# as5311-module.net
KiCad netlist of a schematic drawn in Altium Designer
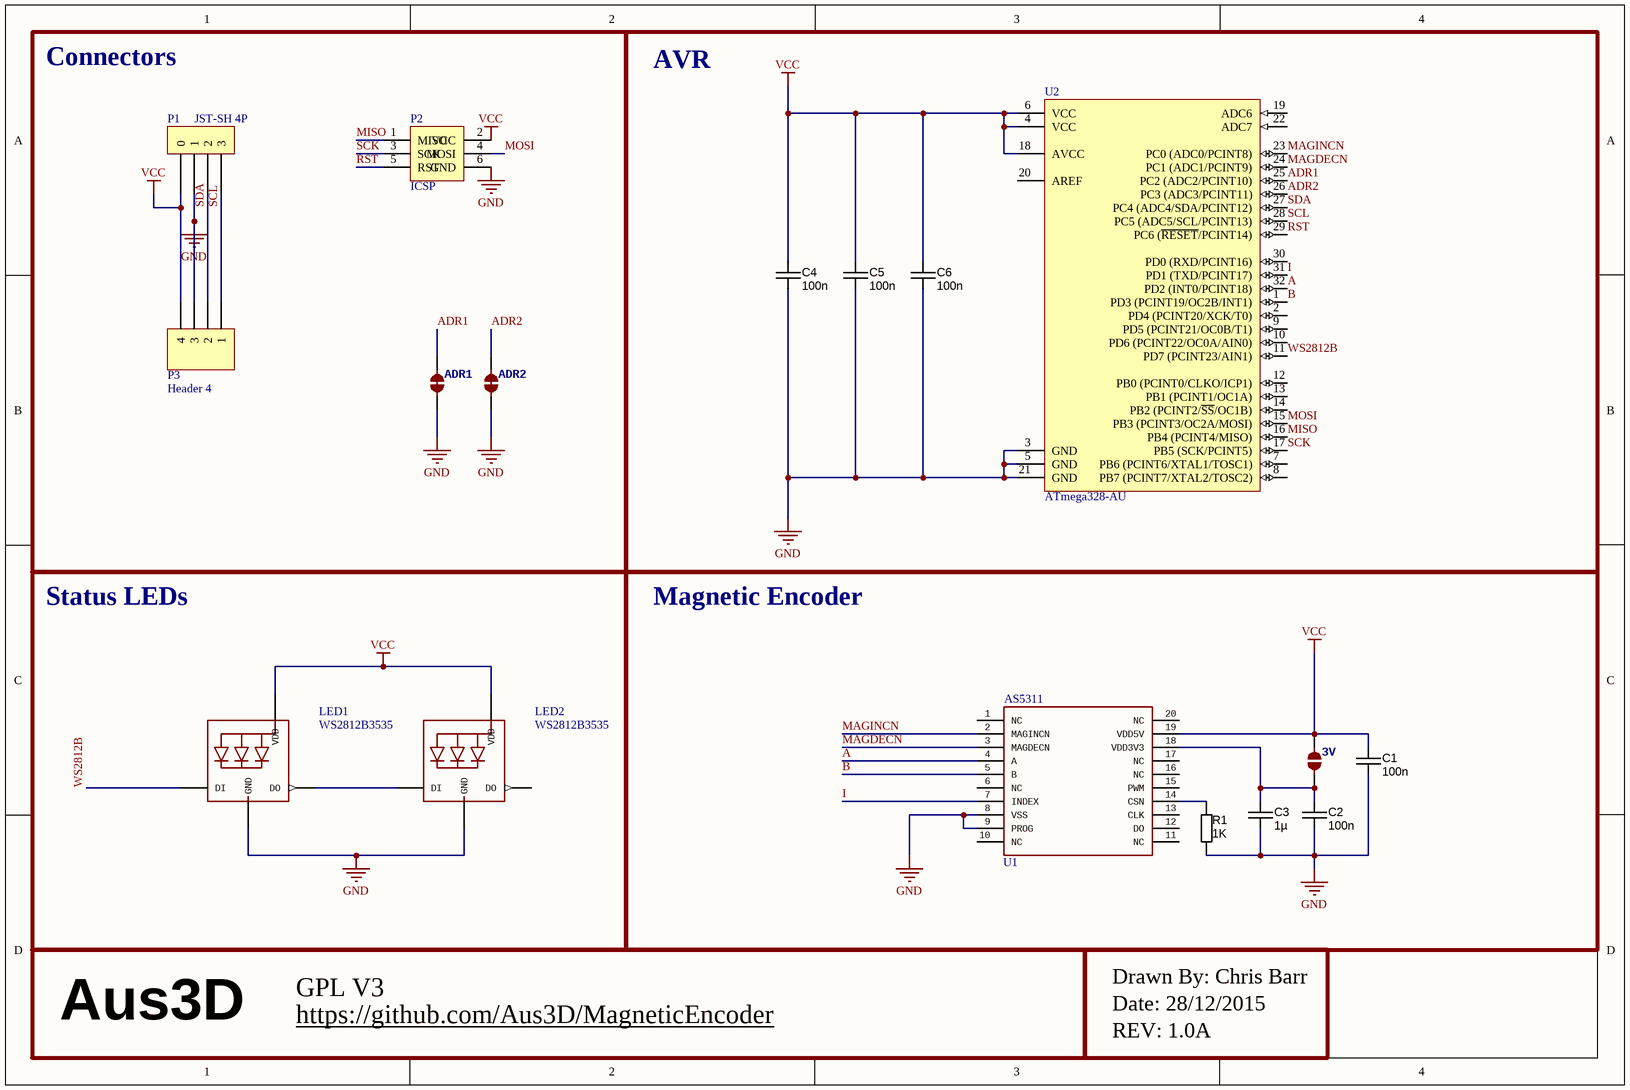
[diagram p0: as5311-module.SchDoc]

(export (version "E")
  (design (tool "Eeschema 10.0.6"))
  (components
    (comp (ref "3V")
      (value "JUMPER-PAD-2-NO")
      (footprint "PAD-JUMPER-2-NO_NO_SILK")
      (libsource (lib "SparkFun-Passives") (part "JUMPER-PAD-2-NO"))
    )
    (comp (ref "ADR1")
      (value "JUMPER-PAD-2-NC_BY_TRACE")
      (footprint "PAD-JUMPER-2-NC_BY_TRACE_YES_SILK")
      (libsource (lib "SparkFun-Passives") (part "JUMPER-PAD-2-NC_BY_TRACE"))
    )
    (comp (ref "ADR2")
      (value "JUMPER-PAD-2-NC_BY_TRACE")
      (footprint "PAD-JUMPER-2-NC_BY_TRACE_YES_SILK")
      (libsource (lib "SparkFun-Passives") (part "JUMPER-PAD-2-NC_BY_TRACE"))
    )
    (comp (ref "C1")
      (value "100n")
      (footprint "CAPC1608X90N")
      (description "Capacitor SMD Cer 100nF 10% 50V X7R 0603")
      (fields (field (name "TOLERANCE") "±10%") (field (name "Comment") "approved sub OK"))
      (libsource (lib "PBL - Capacitors") (part "CAPC_100n_0603_X7R_50V_10%"))
    )
    (comp (ref "C2")
      (value "100n")
      (footprint "CAPC1608X90N")
      (description "Capacitor SMD Cer 100nF 10% 50V X7R 0603")
      (fields (field (name "TOLERANCE") "±10%") (field (name "Comment") "approved sub OK"))
      (libsource (lib "PBL - Capacitors") (part "CAPC_100n_0603_X7R_50V_10%"))
    )
    (comp (ref "C3")
      (value "1µ")
      (footprint "CAPC1608X90N")
      (description "Capacitor SMD Cer 1uF 10% 16V X7R 0603")
      (fields (field (name "TOLERANCE") "±10%") (field (name "Comment") "approved sub OK"))
      (libsource (lib "PBL - Capacitors") (part "CAPC_1u_0603_X7R_16V_10%"))
    )
    (comp (ref "C4")
      (value "100n")
      (footprint "CAPC1608X90N")
      (description "Capacitor SMD Cer 100nF 10% 50V X7R 0603")
      (fields (field (name "TOLERANCE") "±10%") (field (name "Comment") "approved sub OK"))
      (libsource (lib "PBL - Capacitors") (part "CAPC_100n_0603_X7R_50V_10%"))
    )
    (comp (ref "C5")
      (value "100n")
      (footprint "CAPC1608X90N")
      (description "Capacitor SMD Cer 100nF 10% 50V X7R 0603")
      (fields (field (name "TOLERANCE") "±10%") (field (name "Comment") "approved sub OK"))
      (libsource (lib "PBL - Capacitors") (part "CAPC_100n_0603_X7R_50V_10%"))
    )
    (comp (ref "C6")
      (value "100n")
      (footprint "CAPC1608X90N")
      (description "Capacitor SMD Cer 100nF 10% 50V X7R 0603")
      (fields (field (name "TOLERANCE") "±10%") (field (name "Comment") "approved sub OK"))
      (libsource (lib "PBL - Capacitors") (part "CAPC_100n_0603_X7R_50V_10%"))
    )
    (comp (ref "LED1")
      (value "WS2812B3535")
      (footprint "LED3535")
      (libsource (lib "adafruit") (part "WS2812B3535"))
    )
    (comp (ref "LED2")
      (value "WS2812B3535")
      (footprint "LED3535")
      (libsource (lib "adafruit") (part "WS2812B3535"))
    )
    (comp (ref "P1")
      (value "JST-SH 4P")
      (footprint "SM04B-SRSS-TB")
      (libsource (lib "Schlib1") (part "SM04B-SRSS-TB"))
    )
    (comp (ref "P2")
      (value "ICSP")
      (footprint "ICSP Pads - SMD")
      (description "Header, 3-Pin, Dual row")
      (fields (field (name "PUBLISHER") "Altium Limited"))
      (libsource (lib "Miscellaneous Connectors") (part "Header 3X2"))
    )
    (comp (ref "P3")
      (value "Header 4")
      (footprint "HDR1X4")
      (description "Header, 4-Pin")
      (fields (field (name "PUBLISHER") "Altium Limited"))
      (libsource (lib "Miscellaneous Connectors") (part "Header 4"))
    )
    (comp (ref "R1")
      (value "1K")
      (footprint "RESC1608X55N")
      (description "Resistor SMD chip 1k Ohm 0.1W 5% 0603")
      (fields (field (name "TOLERANCE") "±5%") (field (name "Comment") "Thick Film"))
      (libsource (lib "PBL - Resistors") (part "RES_1K_0603_5%"))
    )
    (comp (ref "U1")
      (value "AS5311")
      (footprint "TSSOP-20")
      (description "AMS's AS5311 linear hall-effect encoder.")
      (libsource (lib "ams") (part "AS5311"))
    )
    (comp (ref "U2")
      (value "ATmega328-AU")
      (footprint "32A_N")
      (libsource (lib "Atmel Microcontroller megaAVR") (part "ATmega328-AU"))
    )
  )
  (nets
    (net (code "1") (name "/A") (class "Default")
      (node (ref "U1") (pin "4") (pinfunction "A_4") (pintype "passive"))
      (node (ref "U2") (pin "32") (pinfunction "PD2_(INT0/PCINT18)_32") (pintype "bidirectional"))
    )
    (net (code "2") (name "/ADR1") (class "Default")
      (node (ref "ADR1") (pin "2") (pinfunction "2_2") (pintype "passive"))
      (node (ref "U2") (pin "25") (pinfunction "PC2_(ADC2/PCINT10)_25") (pintype "bidirectional"))
    )
    (net (code "3") (name "/ADR2") (class "Default")
      (node (ref "ADR2") (pin "2") (pinfunction "2_2") (pintype "passive"))
      (node (ref "U2") (pin "26") (pinfunction "PC3_(ADC3/PCINT11)_26") (pintype "bidirectional"))
    )
    (net (code "4") (name "/B") (class "Default")
      (node (ref "U1") (pin "5") (pinfunction "B_5") (pintype "passive"))
      (node (ref "U2") (pin "1") (pinfunction "PD3_(PCINT19/OC2B/INT1)_1") (pintype "bidirectional"))
    )
    (net (code "5") (name "/I") (class "Default")
      (node (ref "U1") (pin "7") (pinfunction "INDEX_7") (pintype "passive"))
      (node (ref "U2") (pin "31") (pinfunction "PD1_(TXD/PCINT17)_31") (pintype "bidirectional"))
    )
    (net (code "6") (name "/MAGDECN") (class "Default")
      (node (ref "U1") (pin "3") (pinfunction "MAGDECN_3") (pintype "passive"))
      (node (ref "U2") (pin "24") (pinfunction "PC1_(ADC1/PCINT9)_24") (pintype "bidirectional"))
    )
    (net (code "7") (name "/MAGINCN") (class "Default")
      (node (ref "U1") (pin "2") (pinfunction "MAGINCN_2") (pintype "passive"))
      (node (ref "U2") (pin "23") (pinfunction "PC0_(ADC0/PCINT8)_23") (pintype "bidirectional"))
    )
    (net (code "8") (name "/MISO") (class "Default")
      (node (ref "P2") (pin "1") (pinfunction "MISO_1") (pintype "passive"))
      (node (ref "U2") (pin "16") (pinfunction "PB4_(PCINT4/MISO)_16") (pintype "bidirectional"))
    )
    (net (code "9") (name "/MOSI") (class "Default")
      (node (ref "P2") (pin "4") (pinfunction "MOSI_4") (pintype "passive"))
      (node (ref "U2") (pin "15") (pinfunction "PB3_(PCINT3/OC2A/MOSI)_15") (pintype "bidirectional"))
    )
    (net (code "10") (name "/RST") (class "Default")
      (node (ref "P2") (pin "5") (pinfunction "RST_5") (pintype "passive"))
      (node (ref "U2") (pin "29") (pinfunction "PC6_(~{RESET}/PCINT14)_29") (pintype "bidirectional"))
    )
    (net (code "11") (name "/SCK") (class "Default")
      (node (ref "P2") (pin "3") (pinfunction "SCK_3") (pintype "passive"))
      (node (ref "U2") (pin "17") (pinfunction "PB5_(SCK/PCINT5)_17") (pintype "bidirectional"))
    )
    (net (code "12") (name "/SCL") (class "Default")
      (node (ref "P1") (pin "3") (pinfunction "3_3") (pintype "passive"))
      (node (ref "P3") (pin "1") (pinfunction "1_1") (pintype "passive"))
      (node (ref "U2") (pin "28") (pinfunction "PC5_(ADC5/SCL/PCINT13)_28") (pintype "bidirectional"))
    )
    (net (code "13") (name "/SDA") (class "Default")
      (node (ref "P1") (pin "2") (pinfunction "2_2") (pintype "passive"))
      (node (ref "P3") (pin "2") (pinfunction "2_2") (pintype "passive"))
      (node (ref "U2") (pin "27") (pinfunction "PC4_(ADC4/SDA/PCINT12)_27") (pintype "bidirectional"))
    )
    (net (code "14") (name "/WS2812B") (class "Default")
      (node (ref "LED1") (pin "1") (pinfunction "DI_1") (pintype "passive"))
      (node (ref "U2") (pin "11") (pinfunction "PD7_(PCINT23/AIN1)_11") (pintype "bidirectional"))
    )
    (net (code "15") (name "GND") (class "Default")
      (node (ref "ADR1") (pin "1") (pinfunction "1_1") (pintype "passive"))
      (node (ref "ADR2") (pin "1") (pinfunction "1_1") (pintype "passive"))
      (node (ref "C1") (pin "2") (pintype "passive"))
      (node (ref "C2") (pin "2") (pintype "passive"))
      (node (ref "C3") (pin "2") (pintype "passive"))
      (node (ref "C4") (pin "2") (pintype "passive"))
      (node (ref "C5") (pin "2") (pintype "passive"))
      (node (ref "C6") (pin "2") (pintype "passive"))
      (node (ref "LED1") (pin "4") (pinfunction "GND_4") (pintype "power_in"))
      (node (ref "LED2") (pin "4") (pinfunction "GND_4") (pintype "power_in"))
      (node (ref "P1") (pin "1") (pinfunction "1_1") (pintype "passive"))
      (node (ref "P2") (pin "6") (pinfunction "GND_6") (pintype "passive"))
      (node (ref "P3") (pin "3") (pinfunction "3_3") (pintype "passive"))
      (node (ref "R1") (pin "2") (pinfunction "2_2") (pintype "passive"))
      (node (ref "U1") (pin "8") (pinfunction "VSS_8") (pintype "power_in"))
      (node (ref "U1") (pin "9") (pinfunction "PROG_9") (pintype "passive"))
      (node (ref "U2") (pin "21") (pinfunction "GND_21") (pintype "power_in"))
      (node (ref "U2") (pin "3") (pinfunction "GND_3") (pintype "power_in"))
      (node (ref "U2") (pin "5") (pinfunction "GND_5") (pintype "power_in"))
    )
    (net (code "16") (name "Net-(LED1-DO)") (class "Default")
      (node (ref "LED1") (pin "3") (pinfunction "DO_3") (pintype "output"))
      (node (ref "LED2") (pin "1") (pinfunction "DI_1") (pintype "passive"))
    )
    (net (code "17") (name "Net-(U1-CSN)") (class "Default")
      (node (ref "R1") (pin "1") (pinfunction "1_1") (pintype "passive"))
      (node (ref "U1") (pin "14") (pinfunction "CSN_14") (pintype "passive"))
    )
    (net (code "18") (name "Net-(U1-VDD3V3)") (class "Default")
      (node (ref "3V") (pin "1") (pinfunction "1_1") (pintype "passive"))
      (node (ref "C2") (pin "1") (pintype "passive"))
      (node (ref "C3") (pin "1") (pintype "passive"))
      (node (ref "U1") (pin "18") (pinfunction "VDD3V3_18") (pintype "open_emitter"))
    )
    (net (code "19") (name "VCC") (class "Default")
      (node (ref "3V") (pin "2") (pinfunction "2_2") (pintype "passive"))
      (node (ref "C1") (pin "1") (pintype "passive"))
      (node (ref "C4") (pin "1") (pintype "passive"))
      (node (ref "C5") (pin "1") (pintype "passive"))
      (node (ref "C6") (pin "1") (pintype "passive"))
      (node (ref "LED1") (pin "2") (pinfunction "VDD_2") (pintype "power_in"))
      (node (ref "LED2") (pin "2") (pinfunction "VDD_2") (pintype "power_in"))
      (node (ref "P1") (pin "0") (pinfunction "0_0") (pintype "passive"))
      (node (ref "P2") (pin "2") (pinfunction "VCC_2") (pintype "passive"))
      (node (ref "P3") (pin "4") (pinfunction "4_4") (pintype "passive"))
      (node (ref "U1") (pin "19") (pinfunction "VDD5V_19") (pintype "open_emitter"))
      (node (ref "U2") (pin "18") (pinfunction "AVCC_18") (pintype "power_in"))
      (node (ref "U2") (pin "4") (pinfunction "VCC_4") (pintype "power_in"))
      (node (ref "U2") (pin "6") (pinfunction "VCC_6") (pintype "power_in"))
    )
    (net (code "20") (name "unconnected-(LED2-DO-Pad3)") (class "Default")
      (node (ref "LED2") (pin "3") (pinfunction "DO_3") (pintype "output"))
    )
    (net (code "21") (name "unconnected-(U1-CLK-Pad13)") (class "Default")
      (node (ref "U1") (pin "13") (pinfunction "CLK_13") (pintype "passive"))
    )
    (net (code "22") (name "unconnected-(U1-DO-Pad12)") (class "Default")
      (node (ref "U1") (pin "12") (pinfunction "DO_12") (pintype "passive"))
    )
    (net (code "23") (name "unconnected-(U1-NC-Pad1)") (class "Default")
      (node (ref "U1") (pin "1") (pinfunction "NC_1") (pintype "passive"))
    )
    (net (code "24") (name "unconnected-(U1-NC-Pad6)") (class "Default")
      (node (ref "U1") (pin "6") (pinfunction "NC_6") (pintype "passive"))
    )
    (net (code "25") (name "unconnected-(U1-NC-Pad10)") (class "Default")
      (node (ref "U1") (pin "10") (pinfunction "NC_10") (pintype "passive"))
    )
    (net (code "26") (name "unconnected-(U1-NC-Pad11)") (class "Default")
      (node (ref "U1") (pin "11") (pinfunction "NC_11") (pintype "passive"))
    )
    (net (code "27") (name "unconnected-(U1-NC-Pad16)") (class "Default")
      (node (ref "U1") (pin "16") (pinfunction "NC_16") (pintype "passive"))
    )
    (net (code "28") (name "unconnected-(U1-NC-Pad17)") (class "Default")
      (node (ref "U1") (pin "17") (pinfunction "NC_17") (pintype "passive"))
    )
    (net (code "29") (name "unconnected-(U1-NC-Pad20)") (class "Default")
      (node (ref "U1") (pin "20") (pinfunction "NC_20") (pintype "passive"))
    )
    (net (code "30") (name "unconnected-(U1-PWM-Pad15)") (class "Default")
      (node (ref "U1") (pin "15") (pinfunction "PWM_15") (pintype "passive"))
    )
    (net (code "31") (name "unconnected-(U2-ADC6-Pad19)") (class "Default")
      (node (ref "U2") (pin "19") (pinfunction "ADC6_19") (pintype "input"))
    )
    (net (code "32") (name "unconnected-(U2-ADC7-Pad22)") (class "Default")
      (node (ref "U2") (pin "22") (pinfunction "ADC7_22") (pintype "input"))
    )
    (net (code "33") (name "unconnected-(U2-AREF-Pad20)") (class "Default")
      (node (ref "U2") (pin "20") (pinfunction "AREF_20") (pintype "passive"))
    )
    (net (code "34") (name "unconnected-(U2-PB0_(PCINT0{slash}CLKO{slash}ICP1)-Pad12)") (class "Default")
      (node (ref "U2") (pin "12") (pinfunction "PB0_(PCINT0/CLKO/ICP1)_12") (pintype "bidirectional"))
    )
    (net (code "35") (name "unconnected-(U2-PB1_(PCINT1{slash}OC1A)-Pad13)") (class "Default")
      (node (ref "U2") (pin "13") (pinfunction "PB1_(PCINT1/OC1A)_13") (pintype "bidirectional"))
    )
    (net (code "36") (name "unconnected-(U2-PB2_(PCINT2{slash}~{SS}{slash}OC1B)-Pad14)") (class "Default")
      (node (ref "U2") (pin "14") (pinfunction "PB2_(PCINT2/~{SS}/OC1B)_14") (pintype "bidirectional"))
    )
    (net (code "37") (name "unconnected-(U2-PB6_(PCINT6{slash}XTAL1{slash}TOSC1)-Pad7)") (class "Default")
      (node (ref "U2") (pin "7") (pinfunction "PB6_(PCINT6/XTAL1/TOSC1)_7") (pintype "bidirectional"))
    )
    (net (code "38") (name "unconnected-(U2-PB7_(PCINT7{slash}XTAL2{slash}TOSC2)-Pad8)") (class "Default")
      (node (ref "U2") (pin "8") (pinfunction "PB7_(PCINT7/XTAL2/TOSC2)_8") (pintype "bidirectional"))
    )
    (net (code "39") (name "unconnected-(U2-PD0_(RXD{slash}PCINT16)-Pad30)") (class "Default")
      (node (ref "U2") (pin "30") (pinfunction "PD0_(RXD/PCINT16)_30") (pintype "bidirectional"))
    )
    (net (code "40") (name "unconnected-(U2-PD4_(PCINT20{slash}XCK{slash}T0)-Pad2)") (class "Default")
      (node (ref "U2") (pin "2") (pinfunction "PD4_(PCINT20/XCK/T0)_2") (pintype "bidirectional"))
    )
    (net (code "41") (name "unconnected-(U2-PD5_(PCINT21{slash}OC0B{slash}T1)-Pad9)") (class "Default")
      (node (ref "U2") (pin "9") (pinfunction "PD5_(PCINT21/OC0B/T1)_9") (pintype "bidirectional"))
    )
    (net (code "42") (name "unconnected-(U2-PD6_(PCINT22{slash}OC0A{slash}AIN0)-Pad10)") (class "Default")
      (node (ref "U2") (pin "10") (pinfunction "PD6_(PCINT22/OC0A/AIN0)_10") (pintype "bidirectional"))
    )
  )
)
